# B001_PCIe_Socket.net
KiCad netlist of a schematic drawn in Altium Designer
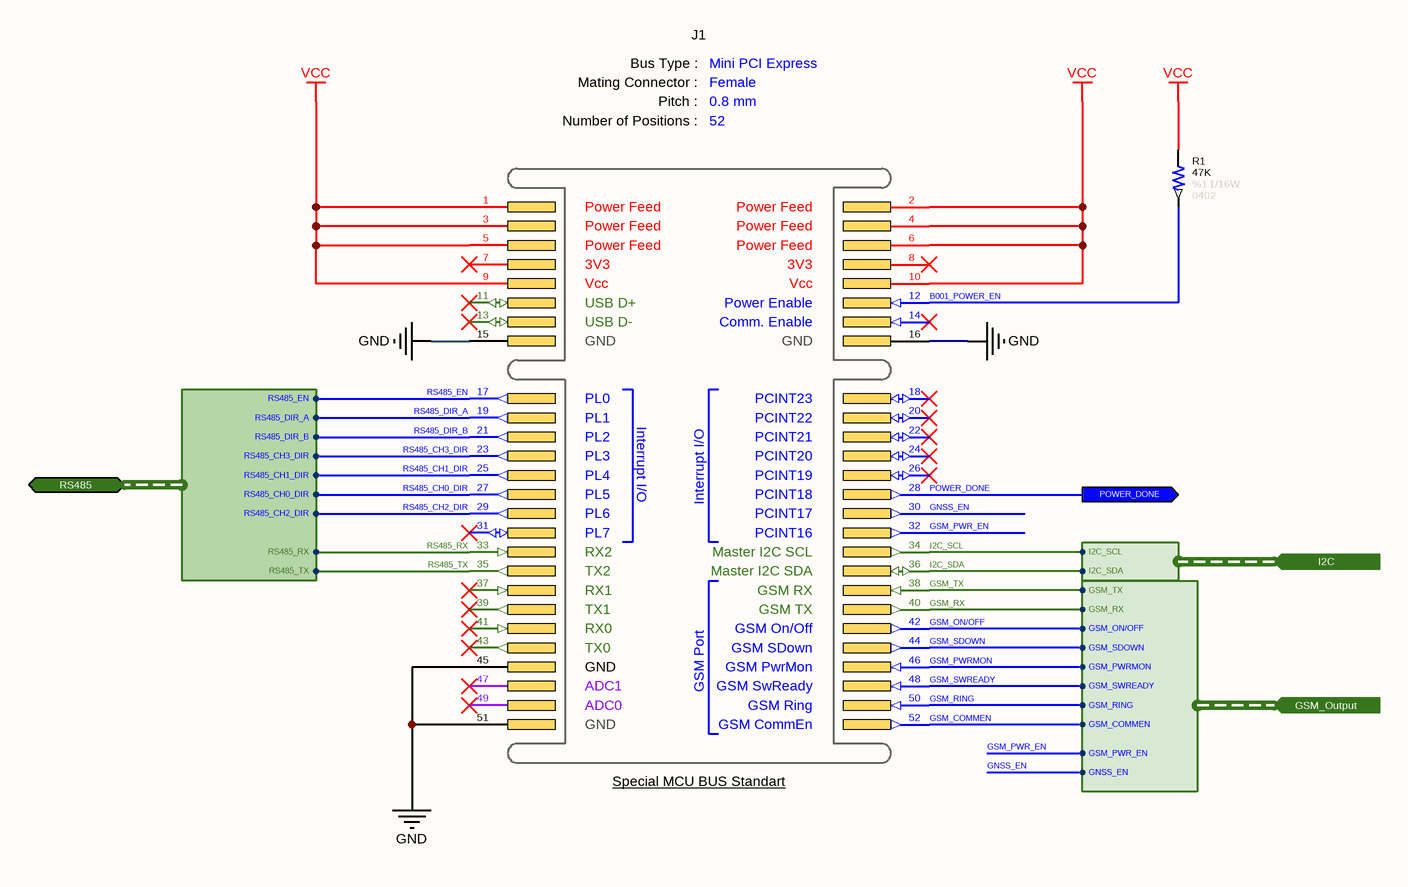
[diagram p0: B001 PCIe Socket.SchDoc]

(export (version "E")
  (design (tool "Eeschema 10.0.6"))
  (components
    (comp (ref "J1")
      (value "TE-1775862-2")
      (footprint "CONNECTOR - Mini PCIe")
      (description "Mini PCI-Express female connector.")
      (fields
        (field (name "BUS TYPE") "Mini PCI Express")
        (field (name "CONNECTOR TYPE") "Female")
        (field (name "PITCH") "0.8 mm")
        (field (name "NUMBER OF POSITIONS") "52")
      )
      (libsource (lib "P101DA_Library") (part "Connector - Mini PCI-E (Female B001)"))
    )
    (comp (ref "R1")
      (value "47K")
      (footprint "RESISTOR_0402")
      (description "Thick Film Resistors - SMD 1/16 W 47 KOhm 1%")
      (fields
        (field (name "MANUFACTURER PART NUMBER") "CRCW040247K0FKED")
        (field (name "TOLERANCE") "%1")
        (field (name "CASE") "0402")
        (field (name "POWER") "1/16W")
        (field (name "Comment") "47K - 0402 - %1 - 1/16W")
      )
      (libsource (lib "P101DA_Library") (part "Resistor - 47K [0402]"))
    )
  )
  (nets
    (net (code "4") (name "/B001_POWER_EN") (class "Default")
      (node (ref "J1") (pin "12") (pinfunction "Pin-12_12") (pintype "input"))
      (node (ref "R1") (pin "1") (pinfunction "1_1") (pintype "output"))
    )
    (net (code "5") (name "/GNSS_EN") (class "Default")
      (node (ref "J1") (pin "30") (pinfunction "Pin-30_30") (pintype "output"))
    )
    (net (code "6") (name "/GSM_COMMEN") (class "Default")
      (node (ref "J1") (pin "52") (pinfunction "Pin-52_52") (pintype "output"))
    )
    (net (code "7") (name "/GSM_ON{slash}OFF") (class "Default")
      (node (ref "J1") (pin "42") (pinfunction "Pin-42_42") (pintype "output"))
    )
    (net (code "8") (name "/GSM_PWRMON") (class "Default")
      (node (ref "J1") (pin "46") (pinfunction "Pin-46_46") (pintype "input"))
    )
    (net (code "9") (name "/GSM_PWR_EN") (class "Default")
      (node (ref "J1") (pin "32") (pinfunction "Pin-32_32") (pintype "output"))
    )
    (net (code "10") (name "/GSM_RING") (class "Default")
      (node (ref "J1") (pin "50") (pinfunction "Pin-50_50") (pintype "input"))
    )
    (net (code "11") (name "/GSM_RX") (class "Default")
      (node (ref "J1") (pin "40") (pinfunction "Pin-40_40") (pintype "output"))
    )
    (net (code "12") (name "/GSM_SDOWN") (class "Default")
      (node (ref "J1") (pin "44") (pinfunction "Pin-44_44") (pintype "output"))
    )
    (net (code "13") (name "/GSM_SWREADY") (class "Default")
      (node (ref "J1") (pin "48") (pinfunction "Pin-48_48") (pintype "input"))
    )
    (net (code "14") (name "/GSM_TX") (class "Default")
      (node (ref "J1") (pin "38") (pinfunction "Pin-38_38") (pintype "input"))
    )
    (net (code "15") (name "/I2C_SCL") (class "Default")
      (node (ref "J1") (pin "34") (pinfunction "Pin-34_34") (pintype "output"))
    )
    (net (code "16") (name "/I2C_SDA") (class "Default")
      (node (ref "J1") (pin "36") (pinfunction "Pin-36_36") (pintype "bidirectional"))
    )
    (net (code "18") (name "/POWER_DONE") (class "Default")
      (node (ref "J1") (pin "28") (pinfunction "Pin-28_28") (pintype "output"))
    )
    (net (code "19") (name "/RS485_CH0_DIR") (class "Default")
      (node (ref "J1") (pin "27") (pinfunction "Pin-27_27") (pintype "output"))
    )
    (net (code "20") (name "/RS485_CH1_DIR") (class "Default")
      (node (ref "J1") (pin "25") (pinfunction "Pin-25_25") (pintype "output"))
    )
    (net (code "21") (name "/RS485_CH2_DIR") (class "Default")
      (node (ref "J1") (pin "29") (pinfunction "Pin-29_29") (pintype "output"))
    )
    (net (code "22") (name "/RS485_CH3_DIR") (class "Default")
      (node (ref "J1") (pin "23") (pinfunction "Pin-23_23") (pintype "output"))
    )
    (net (code "23") (name "/RS485_DIR_A") (class "Default")
      (node (ref "J1") (pin "19") (pinfunction "Pin-19_19") (pintype "output"))
    )
    (net (code "24") (name "/RS485_DIR_B") (class "Default")
      (node (ref "J1") (pin "21") (pinfunction "Pin-21_21") (pintype "output"))
    )
    (net (code "25") (name "/RS485_EN") (class "Default")
      (node (ref "J1") (pin "17") (pinfunction "Pin-17_17") (pintype "output"))
    )
    (net (code "26") (name "/RS485_RX") (class "Default")
      (node (ref "J1") (pin "33") (pinfunction "Pin-33_33") (pintype "input"))
    )
    (net (code "27") (name "/RS485_TX") (class "Default")
      (node (ref "J1") (pin "35") (pinfunction "Pin-35_35") (pintype "output"))
    )
    (net (code "30") (name "GND") (class "Default")
      (node (ref "J1") (pin "15") (pinfunction "Pin-15_15") (pintype "power_in"))
      (node (ref "J1") (pin "16") (pinfunction "Pin-16_16") (pintype "power_in"))
      (node (ref "J1") (pin "45") (pinfunction "Pin-45_45") (pintype "passive"))
      (node (ref "J1") (pin "51") (pinfunction "Pin-51_51") (pintype "power_in"))
    )
    (net (code "31") (name "VCC") (class "Default")
      (node (ref "J1") (pin "1") (pinfunction "Pin-1_1") (pintype "power_in"))
      (node (ref "J1") (pin "10") (pinfunction "Pin-10_10") (pintype "power_in"))
      (node (ref "J1") (pin "2") (pinfunction "Pin-2_2") (pintype "power_in"))
      (node (ref "J1") (pin "3") (pinfunction "Pin-3_3") (pintype "power_in"))
      (node (ref "J1") (pin "4") (pinfunction "Pin-4_4") (pintype "power_in"))
      (node (ref "J1") (pin "5") (pinfunction "Pin-5_5") (pintype "power_in"))
      (node (ref "J1") (pin "6") (pinfunction "Pin-6_6") (pintype "power_in"))
      (node (ref "J1") (pin "9") (pinfunction "Pin-9_9") (pintype "power_in"))
      (node (ref "R1") (pin "2") (pinfunction "2_2") (pintype "passive"))
    )
    (net (code "32") (name "unconnected-(J1-Pin-7-Pad7)") (class "Default")
      (node (ref "J1") (pin "7") (pinfunction "Pin-7_7") (pintype "power_in+no_connect"))
    )
    (net (code "33") (name "unconnected-(J1-Pin-8-Pad8)") (class "Default")
      (node (ref "J1") (pin "8") (pinfunction "Pin-8_8") (pintype "power_in+no_connect"))
    )
    (net (code "34") (name "unconnected-(J1-Pin-11-Pad11)") (class "Default")
      (node (ref "J1") (pin "11") (pinfunction "Pin-11_11") (pintype "bidirectional+no_connect"))
    )
    (net (code "35") (name "unconnected-(J1-Pin-13-Pad13)") (class "Default")
      (node (ref "J1") (pin "13") (pinfunction "Pin-13_13") (pintype "bidirectional+no_connect"))
    )
    (net (code "36") (name "unconnected-(J1-Pin-14-Pad14)") (class "Default")
      (node (ref "J1") (pin "14") (pinfunction "Pin-14_14") (pintype "input+no_connect"))
    )
    (net (code "37") (name "unconnected-(J1-Pin-18-Pad18)") (class "Default")
      (node (ref "J1") (pin "18") (pinfunction "Pin-18_18") (pintype "bidirectional+no_connect"))
    )
    (net (code "38") (name "unconnected-(J1-Pin-20-Pad20)") (class "Default")
      (node (ref "J1") (pin "20") (pinfunction "Pin-20_20") (pintype "bidirectional+no_connect"))
    )
    (net (code "39") (name "unconnected-(J1-Pin-22-Pad22)") (class "Default")
      (node (ref "J1") (pin "22") (pinfunction "Pin-22_22") (pintype "bidirectional+no_connect"))
    )
    (net (code "40") (name "unconnected-(J1-Pin-24-Pad24)") (class "Default")
      (node (ref "J1") (pin "24") (pinfunction "Pin-24_24") (pintype "bidirectional+no_connect"))
    )
    (net (code "41") (name "unconnected-(J1-Pin-26-Pad26)") (class "Default")
      (node (ref "J1") (pin "26") (pinfunction "Pin-26_26") (pintype "bidirectional+no_connect"))
    )
    (net (code "42") (name "unconnected-(J1-Pin-31-Pad31)") (class "Default")
      (node (ref "J1") (pin "31") (pinfunction "Pin-31_31") (pintype "bidirectional+no_connect"))
    )
    (net (code "43") (name "unconnected-(J1-Pin-37-Pad37)") (class "Default")
      (node (ref "J1") (pin "37") (pinfunction "Pin-37_37") (pintype "input+no_connect"))
    )
    (net (code "44") (name "unconnected-(J1-Pin-39-Pad39)") (class "Default")
      (node (ref "J1") (pin "39") (pinfunction "Pin-39_39") (pintype "output+no_connect"))
    )
    (net (code "45") (name "unconnected-(J1-Pin-41-Pad41)") (class "Default")
      (node (ref "J1") (pin "41") (pinfunction "Pin-41_41") (pintype "input+no_connect"))
    )
    (net (code "46") (name "unconnected-(J1-Pin-43-Pad43)") (class "Default")
      (node (ref "J1") (pin "43") (pinfunction "Pin-43_43") (pintype "output+no_connect"))
    )
    (net (code "47") (name "unconnected-(J1-Pin-47-Pad47)") (class "Default")
      (node (ref "J1") (pin "47") (pinfunction "Pin-47_47") (pintype "passive+no_connect"))
    )
    (net (code "48") (name "unconnected-(J1-Pin-49-Pad49)") (class "Default")
      (node (ref "J1") (pin "49") (pinfunction "Pin-49_49") (pintype "passive+no_connect"))
    )
  )
)
